# MX8M-Nano-USB.net
KiCad netlist of a schematic drawn in Altium Designer
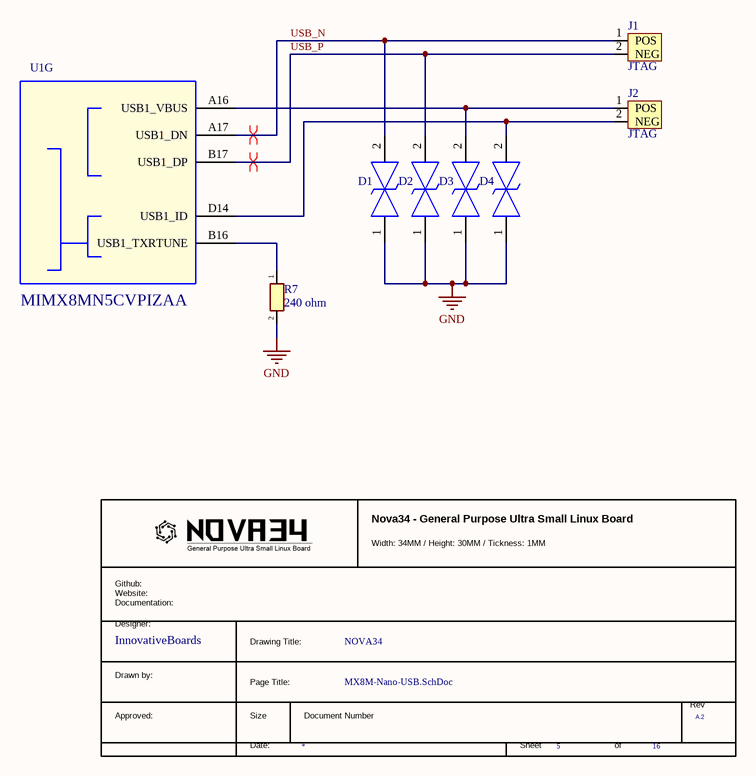
[diagram p0: MX8M-Nano-USB.SchDoc]

(export (version "E")
  (design (tool "Eeschema 10.0.6"))
  (components
    (comp (ref "*")
      (value "TitleBlock_MCPG")
      (fields (field (name "REVCODE") "A.2"))
      (libsource (lib "Nova_SCHLIB") (part "TitleBlock_MCPG"))
    )
    (comp (ref "D1")
      (value "TVS Diode")
      (footprint "SODFL1608X77N")
      (description "TVS Diode (Bi-directional)")
      (fields
        (field (name "MANUFACTURER_PART_NUMBER") "TPD1E10B06DYAR")
        (field (name "MOUSER PART NUMBER") "595-TPD1E10B06DYAR")
      )
      (libsource (lib "Nova_SCHLIB") (part "TPD1E10B06DYAR"))
    )
    (comp (ref "D2")
      (value "TVS Diode")
      (footprint "SODFL1608X77N")
      (description "TVS Diode (Bi-directional)")
      (fields
        (field (name "MANUFACTURER_PART_NUMBER") "TPD1E10B06DYAR")
        (field (name "MOUSER PART NUMBER") "595-TPD1E10B06DYAR")
      )
      (libsource (lib "Nova_SCHLIB") (part "TPD1E10B06DYAR"))
    )
    (comp (ref "D3")
      (value "TVS Diode")
      (footprint "SODFL1608X77N")
      (description "TVS Diode (Bi-directional)")
      (fields
        (field (name "MANUFACTURER_PART_NUMBER") "TPD1E10B06DYAR")
        (field (name "MOUSER PART NUMBER") "595-TPD1E10B06DYAR")
      )
      (libsource (lib "Nova_SCHLIB") (part "TPD1E10B06DYAR"))
    )
    (comp (ref "D4")
      (value "TVS Diode")
      (footprint "SODFL1608X77N")
      (description "TVS Diode (Bi-directional)")
      (fields
        (field (name "MANUFACTURER_PART_NUMBER") "TPD1E10B06DYAR")
        (field (name "MOUSER PART NUMBER") "595-TPD1E10B06DYAR")
      )
      (libsource (lib "Nova_SCHLIB") (part "TPD1E10B06DYAR"))
    )
    (comp (ref "J1") (value "JTAG") (footprint "JTAG") (libsource (lib "Nova_SCHLIB") (part "JTAG")))
    (comp (ref "J2") (value "JTAG") (footprint "JTAG") (libsource (lib "Nova_SCHLIB") (part "JTAG")))
    (comp (ref "R7")
      (value "240 ohm")
      (footprint "RESC0603X26N")
      (description "Resistor")
      (fields
        (field (name "MANUFACTURER_PART_NUMBER") "RC0201FR-07240RL")
        (field (name "MOUSER PART NUMBER") "603-RC0201FR-07240RL")
      )
      (libsource (lib "Nova_SCHLIB") (part "RC0201FR-07240RL"))
    )
    (comp (ref "U1")
      (value "MIMX8MN5CVPIZAA")
      (footprint "BGA306C50P21X21_1100X1100X101")
      (description "IC CPU QUAD CORTEX A53+M7 1.4GHZ -- BGA306")
      (libsource (lib "Nova_SCHLIB") (part "MIMX8MN"))
    )
  )
  (nets
    (net (code "1") (name "/USB_N") (class "Default")
      (node (ref "D1") (pin "2") (pinfunction "2_2") (pintype "passive"))
      (node (ref "J1") (pin "1") (pinfunction "POS_1") (pintype "passive"))
      (node (ref "U1") (pin "A17") (pinfunction "USB1_DN_A17") (pintype "passive"))
    )
    (net (code "2") (name "/USB_P") (class "Default")
      (node (ref "D2") (pin "2") (pinfunction "2_2") (pintype "passive"))
      (node (ref "J1") (pin "2") (pinfunction "NEG_2") (pintype "passive"))
      (node (ref "U1") (pin "B17") (pinfunction "USB1_DP_B17") (pintype "passive"))
    )
    (net (code "3") (name "GND") (class "Default")
      (node (ref "D1") (pin "1") (pinfunction "1_1") (pintype "passive"))
      (node (ref "D2") (pin "1") (pinfunction "1_1") (pintype "passive"))
      (node (ref "D3") (pin "1") (pinfunction "1_1") (pintype "passive"))
      (node (ref "D4") (pin "1") (pinfunction "1_1") (pintype "passive"))
      (node (ref "R7") (pin "2") (pinfunction "2_2") (pintype "passive"))
    )
    (net (code "4") (name "Net-(J2-NEG)") (class "Default")
      (node (ref "D4") (pin "2") (pinfunction "2_2") (pintype "passive"))
      (node (ref "J2") (pin "2") (pinfunction "NEG_2") (pintype "passive"))
      (node (ref "U1") (pin "D14") (pinfunction "USB1_ID_D14") (pintype "passive"))
    )
    (net (code "5") (name "Net-(J2-POS)") (class "Default")
      (node (ref "D3") (pin "2") (pinfunction "2_2") (pintype "passive"))
      (node (ref "J2") (pin "1") (pinfunction "POS_1") (pintype "passive"))
      (node (ref "U1") (pin "A16") (pinfunction "USB1_VBUS_A16") (pintype "passive"))
    )
    (net (code "6") (name "Net-(U1G-USB1_TXRTUNE)") (class "Default")
      (node (ref "R7") (pin "1") (pinfunction "1_1") (pintype "passive"))
      (node (ref "U1") (pin "B16") (pinfunction "USB1_TXRTUNE_B16") (pintype "passive"))
    )
  )
)
